# Vout.net
KiCad netlist of a schematic drawn in Altium Designer
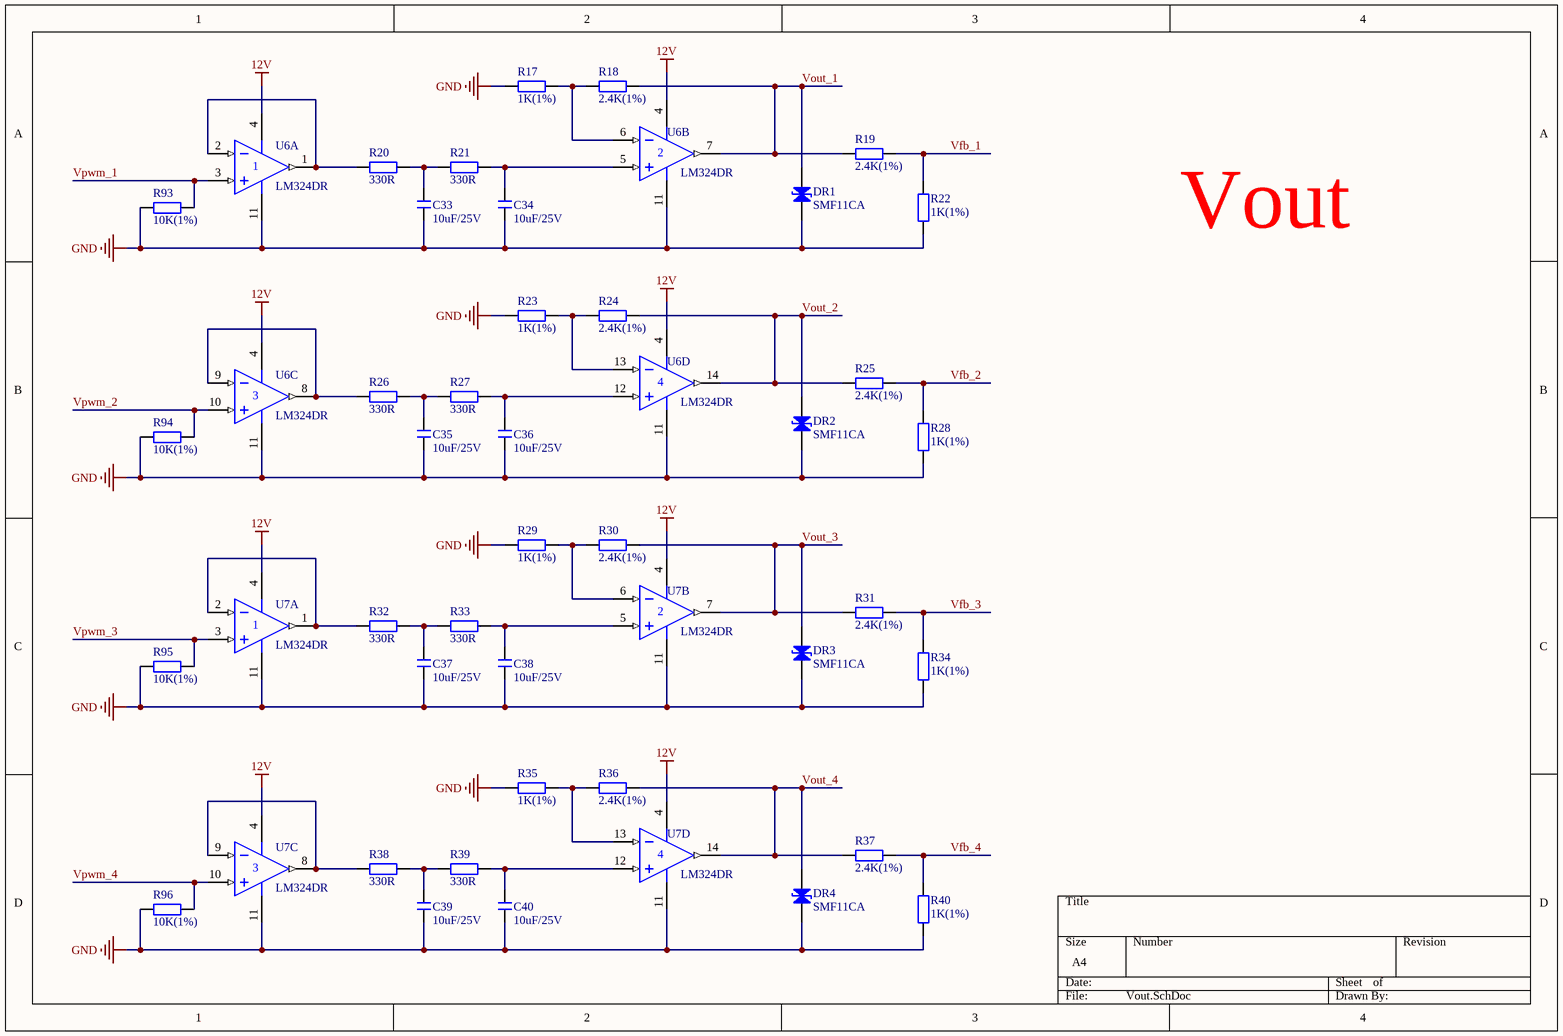
[diagram p0: Vout.SchDoc]

(export (version "E")
  (design (tool "Eeschema 10.0.6"))
  (components
    (comp (ref "C33")
      (value "10uF/25V")
      (footprint "C 0603_L")
      (description "无极性贴片电容")
      (fields (field (name "版权归属") "源创客"))
      (libsource (lib "电阻-电容-电感") (part "C"))
    )
    (comp (ref "C34")
      (value "10uF/25V")
      (footprint "C 0603_L")
      (description "无极性贴片电容")
      (fields (field (name "版权归属") "源创客"))
      (libsource (lib "电阻-电容-电感") (part "C"))
    )
    (comp (ref "C35")
      (value "10uF/25V")
      (footprint "C 0603_L")
      (description "无极性贴片电容")
      (fields (field (name "版权归属") "源创客"))
      (libsource (lib "电阻-电容-电感") (part "C"))
    )
    (comp (ref "C36")
      (value "10uF/25V")
      (footprint "C 0603_L")
      (description "无极性贴片电容")
      (fields (field (name "版权归属") "源创客"))
      (libsource (lib "电阻-电容-电感") (part "C"))
    )
    (comp (ref "C37")
      (value "10uF/25V")
      (footprint "C 0603_L")
      (description "无极性贴片电容")
      (fields (field (name "版权归属") "源创客"))
      (libsource (lib "电阻-电容-电感") (part "C"))
    )
    (comp (ref "C38")
      (value "10uF/25V")
      (footprint "C 0603_L")
      (description "无极性贴片电容")
      (fields (field (name "版权归属") "源创客"))
      (libsource (lib "电阻-电容-电感") (part "C"))
    )
    (comp (ref "C39")
      (value "10uF/25V")
      (footprint "C 0603_L")
      (description "无极性贴片电容")
      (fields (field (name "版权归属") "源创客"))
      (libsource (lib "电阻-电容-电感") (part "C"))
    )
    (comp (ref "C40")
      (value "10uF/25V")
      (footprint "C 0603_L")
      (description "无极性贴片电容")
      (fields (field (name "版权归属") "源创客"))
      (libsource (lib "电阻-电容-电感") (part "C"))
    )
    (comp (ref "DR1")
      (value "SMF11CA")
      (footprint "SOD-123F")
      (description "瞬态电压抑制二极管")
      (fields (field (name "版权归属") "源创客"))
      (libsource (lib "二极管-整流桥") (part "DR"))
    )
    (comp (ref "DR2")
      (value "SMF11CA")
      (footprint "SOD-123F")
      (description "瞬态电压抑制二极管")
      (fields (field (name "版权归属") "源创客"))
      (libsource (lib "二极管-整流桥") (part "DR"))
    )
    (comp (ref "DR3")
      (value "SMF11CA")
      (footprint "SOD-123F")
      (description "瞬态电压抑制二极管")
      (fields (field (name "版权归属") "源创客"))
      (libsource (lib "二极管-整流桥") (part "DR"))
    )
    (comp (ref "DR4")
      (value "SMF11CA")
      (footprint "SOD-123F")
      (description "瞬态电压抑制二极管")
      (fields (field (name "版权归属") "源创客"))
      (libsource (lib "二极管-整流桥") (part "DR"))
    )
    (comp (ref "R17")
      (value "1K(1%)")
      (footprint "R 0603_L")
      (description "贴片电阻")
      (fields (field (name "版权归属") "源创客"))
      (libsource (lib "电阻-电容-电感") (part "R"))
    )
    (comp (ref "R18")
      (value "2.4K(1%)")
      (footprint "R 0603_L")
      (description "贴片电阻")
      (fields (field (name "版权归属") "源创客"))
      (libsource (lib "电阻-电容-电感") (part "R"))
    )
    (comp (ref "R19")
      (value "2.4K(1%)")
      (footprint "R 0603_L")
      (description "贴片电阻")
      (fields (field (name "版权归属") "源创客"))
      (libsource (lib "电阻-电容-电感") (part "R"))
    )
    (comp (ref "R20")
      (value "330R")
      (footprint "R 0603_L")
      (description "贴片电阻")
      (fields (field (name "版权归属") "源创客"))
      (libsource (lib "电阻-电容-电感") (part "R"))
    )
    (comp (ref "R21")
      (value "330R")
      (footprint "R 0603_L")
      (description "贴片电阻")
      (fields (field (name "版权归属") "源创客"))
      (libsource (lib "电阻-电容-电感") (part "R"))
    )
    (comp (ref "R22")
      (value "1K(1%)")
      (footprint "R 0603_L")
      (description "贴片电阻")
      (fields (field (name "版权归属") "源创客"))
      (libsource (lib "电阻-电容-电感") (part "R"))
    )
    (comp (ref "R23")
      (value "1K(1%)")
      (footprint "R 0603_L")
      (description "贴片电阻")
      (fields (field (name "版权归属") "源创客"))
      (libsource (lib "电阻-电容-电感") (part "R"))
    )
    (comp (ref "R24")
      (value "2.4K(1%)")
      (footprint "R 0603_L")
      (description "贴片电阻")
      (fields (field (name "版权归属") "源创客"))
      (libsource (lib "电阻-电容-电感") (part "R"))
    )
    (comp (ref "R25")
      (value "2.4K(1%)")
      (footprint "R 0603_L")
      (description "贴片电阻")
      (fields (field (name "版权归属") "源创客"))
      (libsource (lib "电阻-电容-电感") (part "R"))
    )
    (comp (ref "R26")
      (value "330R")
      (footprint "R 0603_L")
      (description "贴片电阻")
      (fields (field (name "版权归属") "源创客"))
      (libsource (lib "电阻-电容-电感") (part "R"))
    )
    (comp (ref "R27")
      (value "330R")
      (footprint "R 0603_L")
      (description "贴片电阻")
      (fields (field (name "版权归属") "源创客"))
      (libsource (lib "电阻-电容-电感") (part "R"))
    )
    (comp (ref "R28")
      (value "1K(1%)")
      (footprint "R 0603_L")
      (description "贴片电阻")
      (fields (field (name "版权归属") "源创客"))
      (libsource (lib "电阻-电容-电感") (part "R"))
    )
    (comp (ref "R29")
      (value "1K(1%)")
      (footprint "R 0603_L")
      (description "贴片电阻")
      (fields (field (name "版权归属") "源创客"))
      (libsource (lib "电阻-电容-电感") (part "R"))
    )
    (comp (ref "R30")
      (value "2.4K(1%)")
      (footprint "R 0603_L")
      (description "贴片电阻")
      (fields (field (name "版权归属") "源创客"))
      (libsource (lib "电阻-电容-电感") (part "R"))
    )
    (comp (ref "R31")
      (value "2.4K(1%)")
      (footprint "R 0603_L")
      (description "贴片电阻")
      (fields (field (name "版权归属") "源创客"))
      (libsource (lib "电阻-电容-电感") (part "R"))
    )
    (comp (ref "R32")
      (value "330R")
      (footprint "R 0603_L")
      (description "贴片电阻")
      (fields (field (name "版权归属") "源创客"))
      (libsource (lib "电阻-电容-电感") (part "R"))
    )
    (comp (ref "R33")
      (value "330R")
      (footprint "R 0603_L")
      (description "贴片电阻")
      (fields (field (name "版权归属") "源创客"))
      (libsource (lib "电阻-电容-电感") (part "R"))
    )
    (comp (ref "R34")
      (value "1K(1%)")
      (footprint "R 0603_L")
      (description "贴片电阻")
      (fields (field (name "版权归属") "源创客"))
      (libsource (lib "电阻-电容-电感") (part "R"))
    )
    (comp (ref "R35")
      (value "1K(1%)")
      (footprint "R 0603_L")
      (description "贴片电阻")
      (fields (field (name "版权归属") "源创客"))
      (libsource (lib "电阻-电容-电感") (part "R"))
    )
    (comp (ref "R36")
      (value "2.4K(1%)")
      (footprint "R 0603_L")
      (description "贴片电阻")
      (fields (field (name "版权归属") "源创客"))
      (libsource (lib "电阻-电容-电感") (part "R"))
    )
    (comp (ref "R37")
      (value "2.4K(1%)")
      (footprint "R 0603_L")
      (description "贴片电阻")
      (fields (field (name "版权归属") "源创客"))
      (libsource (lib "电阻-电容-电感") (part "R"))
    )
    (comp (ref "R38")
      (value "330R")
      (footprint "R 0603_L")
      (description "贴片电阻")
      (fields (field (name "版权归属") "源创客"))
      (libsource (lib "电阻-电容-电感") (part "R"))
    )
    (comp (ref "R39")
      (value "330R")
      (footprint "R 0603_L")
      (description "贴片电阻")
      (fields (field (name "版权归属") "源创客"))
      (libsource (lib "电阻-电容-电感") (part "R"))
    )
    (comp (ref "R40")
      (value "1K(1%)")
      (footprint "R 0603_L")
      (description "贴片电阻")
      (fields (field (name "版权归属") "源创客"))
      (libsource (lib "电阻-电容-电感") (part "R"))
    )
    (comp (ref "R93")
      (value "10K(1%)")
      (footprint "R 0603_L")
      (description "贴片电阻")
      (fields (field (name "版权归属") "源创客"))
      (libsource (lib "电阻-电容-电感") (part "R"))
    )
    (comp (ref "R94")
      (value "10K(1%)")
      (footprint "R 0603_L")
      (description "贴片电阻")
      (fields (field (name "版权归属") "源创客"))
      (libsource (lib "电阻-电容-电感") (part "R"))
    )
    (comp (ref "R95")
      (value "10K(1%)")
      (footprint "R 0603_L")
      (description "贴片电阻")
      (fields (field (name "版权归属") "源创客"))
      (libsource (lib "电阻-电容-电感") (part "R"))
    )
    (comp (ref "R96")
      (value "10K(1%)")
      (footprint "R 0603_L")
      (description "贴片电阻")
      (fields (field (name "版权归属") "源创客"))
      (libsource (lib "电阻-电容-电感") (part "R"))
    )
    (comp (ref "U6")
      (value "LM324DR")
      (footprint "D014_N")
      (description "Quadruple Operational Amplifier")
      (fields (field (name "PUBLISHER") "Altium Limited"))
      (libsource (lib "MICB") (part "LM324DR"))
    )
    (comp (ref "U7")
      (value "LM324DR")
      (footprint "D014_N")
      (description "Quadruple Operational Amplifier")
      (fields (field (name "PUBLISHER") "Altium Limited"))
      (libsource (lib "MICB") (part "LM324DR"))
    )
  )
  (nets
    (net (code "1") (name "/Vfb_1") (class "Default")
      (node (ref "R19") (pin "1") (pinfunction "1_1") (pintype "passive"))
      (node (ref "R22") (pin "2") (pinfunction "2_2") (pintype "passive"))
    )
    (net (code "2") (name "/Vfb_2") (class "Default")
      (node (ref "R25") (pin "1") (pinfunction "1_1") (pintype "passive"))
      (node (ref "R28") (pin "2") (pinfunction "2_2") (pintype "passive"))
    )
    (net (code "3") (name "/Vfb_3") (class "Default")
      (node (ref "R31") (pin "1") (pinfunction "1_1") (pintype "passive"))
      (node (ref "R34") (pin "2") (pinfunction "2_2") (pintype "passive"))
    )
    (net (code "4") (name "/Vfb_4") (class "Default")
      (node (ref "R37") (pin "1") (pinfunction "1_1") (pintype "passive"))
      (node (ref "R40") (pin "2") (pinfunction "2_2") (pintype "passive"))
    )
    (net (code "5") (name "/Vout_1") (class "Default")
      (node (ref "DR1") (pin "1") (pinfunction "A_1") (pintype "passive"))
      (node (ref "R18") (pin "1") (pinfunction "1_1") (pintype "passive"))
      (node (ref "R19") (pin "2") (pinfunction "2_2") (pintype "passive"))
      (node (ref "U6") (pin "7") (pinfunction "OUT_7") (pintype "output"))
    )
    (net (code "6") (name "/Vout_2") (class "Default")
      (node (ref "DR2") (pin "1") (pinfunction "A_1") (pintype "passive"))
      (node (ref "R24") (pin "1") (pinfunction "1_1") (pintype "passive"))
      (node (ref "R25") (pin "2") (pinfunction "2_2") (pintype "passive"))
      (node (ref "U6") (pin "14") (pinfunction "OUT_14") (pintype "output"))
    )
    (net (code "7") (name "/Vout_3") (class "Default")
      (node (ref "DR3") (pin "1") (pinfunction "A_1") (pintype "passive"))
      (node (ref "R30") (pin "1") (pinfunction "1_1") (pintype "passive"))
      (node (ref "R31") (pin "2") (pinfunction "2_2") (pintype "passive"))
      (node (ref "U7") (pin "7") (pinfunction "OUT_7") (pintype "output"))
    )
    (net (code "8") (name "/Vout_4") (class "Default")
      (node (ref "DR4") (pin "1") (pinfunction "A_1") (pintype "passive"))
      (node (ref "R36") (pin "1") (pinfunction "1_1") (pintype "passive"))
      (node (ref "R37") (pin "2") (pinfunction "2_2") (pintype "passive"))
      (node (ref "U7") (pin "14") (pinfunction "OUT_14") (pintype "output"))
    )
    (net (code "9") (name "/Vpwm_1") (class "Default")
      (node (ref "R93") (pin "2") (pinfunction "2_2") (pintype "passive"))
      (node (ref "U6") (pin "3") (pinfunction "IN+_3") (pintype "input"))
    )
    (net (code "10") (name "/Vpwm_2") (class "Default")
      (node (ref "R94") (pin "2") (pinfunction "2_2") (pintype "passive"))
      (node (ref "U6") (pin "10") (pinfunction "IN+_10") (pintype "input"))
    )
    (net (code "11") (name "/Vpwm_3") (class "Default")
      (node (ref "R95") (pin "2") (pinfunction "2_2") (pintype "passive"))
      (node (ref "U7") (pin "3") (pinfunction "IN+_3") (pintype "input"))
    )
    (net (code "12") (name "/Vpwm_4") (class "Default")
      (node (ref "R96") (pin "2") (pinfunction "2_2") (pintype "passive"))
      (node (ref "U7") (pin "10") (pinfunction "IN+_10") (pintype "input"))
    )
    (net (code "13") (name "12V") (class "Default")
      (node (ref "U6") (pin "4") (pinfunction "V+_4") (pintype "power_in"))
      (node (ref "U7") (pin "4") (pinfunction "V+_4") (pintype "power_in"))
    )
    (net (code "14") (name "GND") (class "Default")
      (node (ref "C33") (pin "1") (pinfunction "1_1") (pintype "passive"))
      (node (ref "C34") (pin "1") (pinfunction "1_1") (pintype "passive"))
      (node (ref "C35") (pin "1") (pinfunction "1_1") (pintype "passive"))
      (node (ref "C36") (pin "1") (pinfunction "1_1") (pintype "passive"))
      (node (ref "C37") (pin "1") (pinfunction "1_1") (pintype "passive"))
      (node (ref "C38") (pin "1") (pinfunction "1_1") (pintype "passive"))
      (node (ref "C39") (pin "1") (pinfunction "1_1") (pintype "passive"))
      (node (ref "C40") (pin "1") (pinfunction "1_1") (pintype "passive"))
      (node (ref "DR1") (pin "2") (pinfunction "K_2") (pintype "passive"))
      (node (ref "DR2") (pin "2") (pinfunction "K_2") (pintype "passive"))
      (node (ref "DR3") (pin "2") (pinfunction "K_2") (pintype "passive"))
      (node (ref "DR4") (pin "2") (pinfunction "K_2") (pintype "passive"))
      (node (ref "R17") (pin "2") (pinfunction "2_2") (pintype "passive"))
      (node (ref "R22") (pin "1") (pinfunction "1_1") (pintype "passive"))
      (node (ref "R23") (pin "2") (pinfunction "2_2") (pintype "passive"))
      (node (ref "R28") (pin "1") (pinfunction "1_1") (pintype "passive"))
      (node (ref "R29") (pin "2") (pinfunction "2_2") (pintype "passive"))
      (node (ref "R34") (pin "1") (pinfunction "1_1") (pintype "passive"))
      (node (ref "R35") (pin "2") (pinfunction "2_2") (pintype "passive"))
      (node (ref "R40") (pin "1") (pinfunction "1_1") (pintype "passive"))
      (node (ref "R93") (pin "1") (pinfunction "1_1") (pintype "passive"))
      (node (ref "R94") (pin "1") (pinfunction "1_1") (pintype "passive"))
      (node (ref "R95") (pin "1") (pinfunction "1_1") (pintype "passive"))
      (node (ref "R96") (pin "1") (pinfunction "1_1") (pintype "passive"))
      (node (ref "U6") (pin "11") (pinfunction "V-_11") (pintype "power_in"))
      (node (ref "U7") (pin "11") (pinfunction "V-_11") (pintype "power_in"))
    )
    (net (code "15") (name "Net-(C33-Pad2)") (class "Default")
      (node (ref "C33") (pin "2") (pinfunction "2_2") (pintype "passive"))
      (node (ref "R20") (pin "1") (pinfunction "1_1") (pintype "passive"))
      (node (ref "R21") (pin "2") (pinfunction "2_2") (pintype "passive"))
    )
    (net (code "16") (name "Net-(C35-Pad2)") (class "Default")
      (node (ref "C35") (pin "2") (pinfunction "2_2") (pintype "passive"))
      (node (ref "R26") (pin "1") (pinfunction "1_1") (pintype "passive"))
      (node (ref "R27") (pin "2") (pinfunction "2_2") (pintype "passive"))
    )
    (net (code "17") (name "Net-(C37-Pad2)") (class "Default")
      (node (ref "C37") (pin "2") (pinfunction "2_2") (pintype "passive"))
      (node (ref "R32") (pin "1") (pinfunction "1_1") (pintype "passive"))
      (node (ref "R33") (pin "2") (pinfunction "2_2") (pintype "passive"))
    )
    (net (code "18") (name "Net-(C39-Pad2)") (class "Default")
      (node (ref "C39") (pin "2") (pinfunction "2_2") (pintype "passive"))
      (node (ref "R38") (pin "1") (pinfunction "1_1") (pintype "passive"))
      (node (ref "R39") (pin "2") (pinfunction "2_2") (pintype "passive"))
    )
    (net (code "19") (name "Net-(U6A-IN-)") (class "Default")
      (node (ref "R20") (pin "2") (pinfunction "2_2") (pintype "passive"))
      (node (ref "U6") (pin "1") (pinfunction "OUT_1") (pintype "output"))
      (node (ref "U6") (pin "2") (pinfunction "IN-_2") (pintype "input"))
    )
    (net (code "20") (name "Net-(U6B-IN+)") (class "Default")
      (node (ref "C34") (pin "2") (pinfunction "2_2") (pintype "passive"))
      (node (ref "R21") (pin "1") (pinfunction "1_1") (pintype "passive"))
      (node (ref "U6") (pin "5") (pinfunction "IN+_5") (pintype "input"))
    )
    (net (code "21") (name "Net-(U6B-IN-)") (class "Default")
      (node (ref "R17") (pin "1") (pinfunction "1_1") (pintype "passive"))
      (node (ref "R18") (pin "2") (pinfunction "2_2") (pintype "passive"))
      (node (ref "U6") (pin "6") (pinfunction "IN-_6") (pintype "input"))
    )
    (net (code "22") (name "Net-(U6C-IN-)") (class "Default")
      (node (ref "R26") (pin "2") (pinfunction "2_2") (pintype "passive"))
      (node (ref "U6") (pin "8") (pinfunction "OUT_8") (pintype "output"))
      (node (ref "U6") (pin "9") (pinfunction "IN-_9") (pintype "input"))
    )
    (net (code "23") (name "Net-(U6D-IN+)") (class "Default")
      (node (ref "C36") (pin "2") (pinfunction "2_2") (pintype "passive"))
      (node (ref "R27") (pin "1") (pinfunction "1_1") (pintype "passive"))
      (node (ref "U6") (pin "12") (pinfunction "IN+_12") (pintype "input"))
    )
    (net (code "24") (name "Net-(U6D-IN-)") (class "Default")
      (node (ref "R23") (pin "1") (pinfunction "1_1") (pintype "passive"))
      (node (ref "R24") (pin "2") (pinfunction "2_2") (pintype "passive"))
      (node (ref "U6") (pin "13") (pinfunction "IN-_13") (pintype "input"))
    )
    (net (code "25") (name "Net-(U7A-IN-)") (class "Default")
      (node (ref "R32") (pin "2") (pinfunction "2_2") (pintype "passive"))
      (node (ref "U7") (pin "1") (pinfunction "OUT_1") (pintype "output"))
      (node (ref "U7") (pin "2") (pinfunction "IN-_2") (pintype "input"))
    )
    (net (code "26") (name "Net-(U7B-IN+)") (class "Default")
      (node (ref "C38") (pin "2") (pinfunction "2_2") (pintype "passive"))
      (node (ref "R33") (pin "1") (pinfunction "1_1") (pintype "passive"))
      (node (ref "U7") (pin "5") (pinfunction "IN+_5") (pintype "input"))
    )
    (net (code "27") (name "Net-(U7B-IN-)") (class "Default")
      (node (ref "R29") (pin "1") (pinfunction "1_1") (pintype "passive"))
      (node (ref "R30") (pin "2") (pinfunction "2_2") (pintype "passive"))
      (node (ref "U7") (pin "6") (pinfunction "IN-_6") (pintype "input"))
    )
    (net (code "28") (name "Net-(U7C-IN-)") (class "Default")
      (node (ref "R38") (pin "2") (pinfunction "2_2") (pintype "passive"))
      (node (ref "U7") (pin "8") (pinfunction "OUT_8") (pintype "output"))
      (node (ref "U7") (pin "9") (pinfunction "IN-_9") (pintype "input"))
    )
    (net (code "29") (name "Net-(U7D-IN+)") (class "Default")
      (node (ref "C40") (pin "2") (pinfunction "2_2") (pintype "passive"))
      (node (ref "R39") (pin "1") (pinfunction "1_1") (pintype "passive"))
      (node (ref "U7") (pin "12") (pinfunction "IN+_12") (pintype "input"))
    )
    (net (code "30") (name "Net-(U7D-IN-)") (class "Default")
      (node (ref "R35") (pin "1") (pinfunction "1_1") (pintype "passive"))
      (node (ref "R36") (pin "2") (pinfunction "2_2") (pintype "passive"))
      (node (ref "U7") (pin "13") (pinfunction "IN-_13") (pintype "input"))
    )
  )
)
